# Condor2_80_Pin_REV_C.net
KiCad netlist of a schematic drawn in Altium Designer
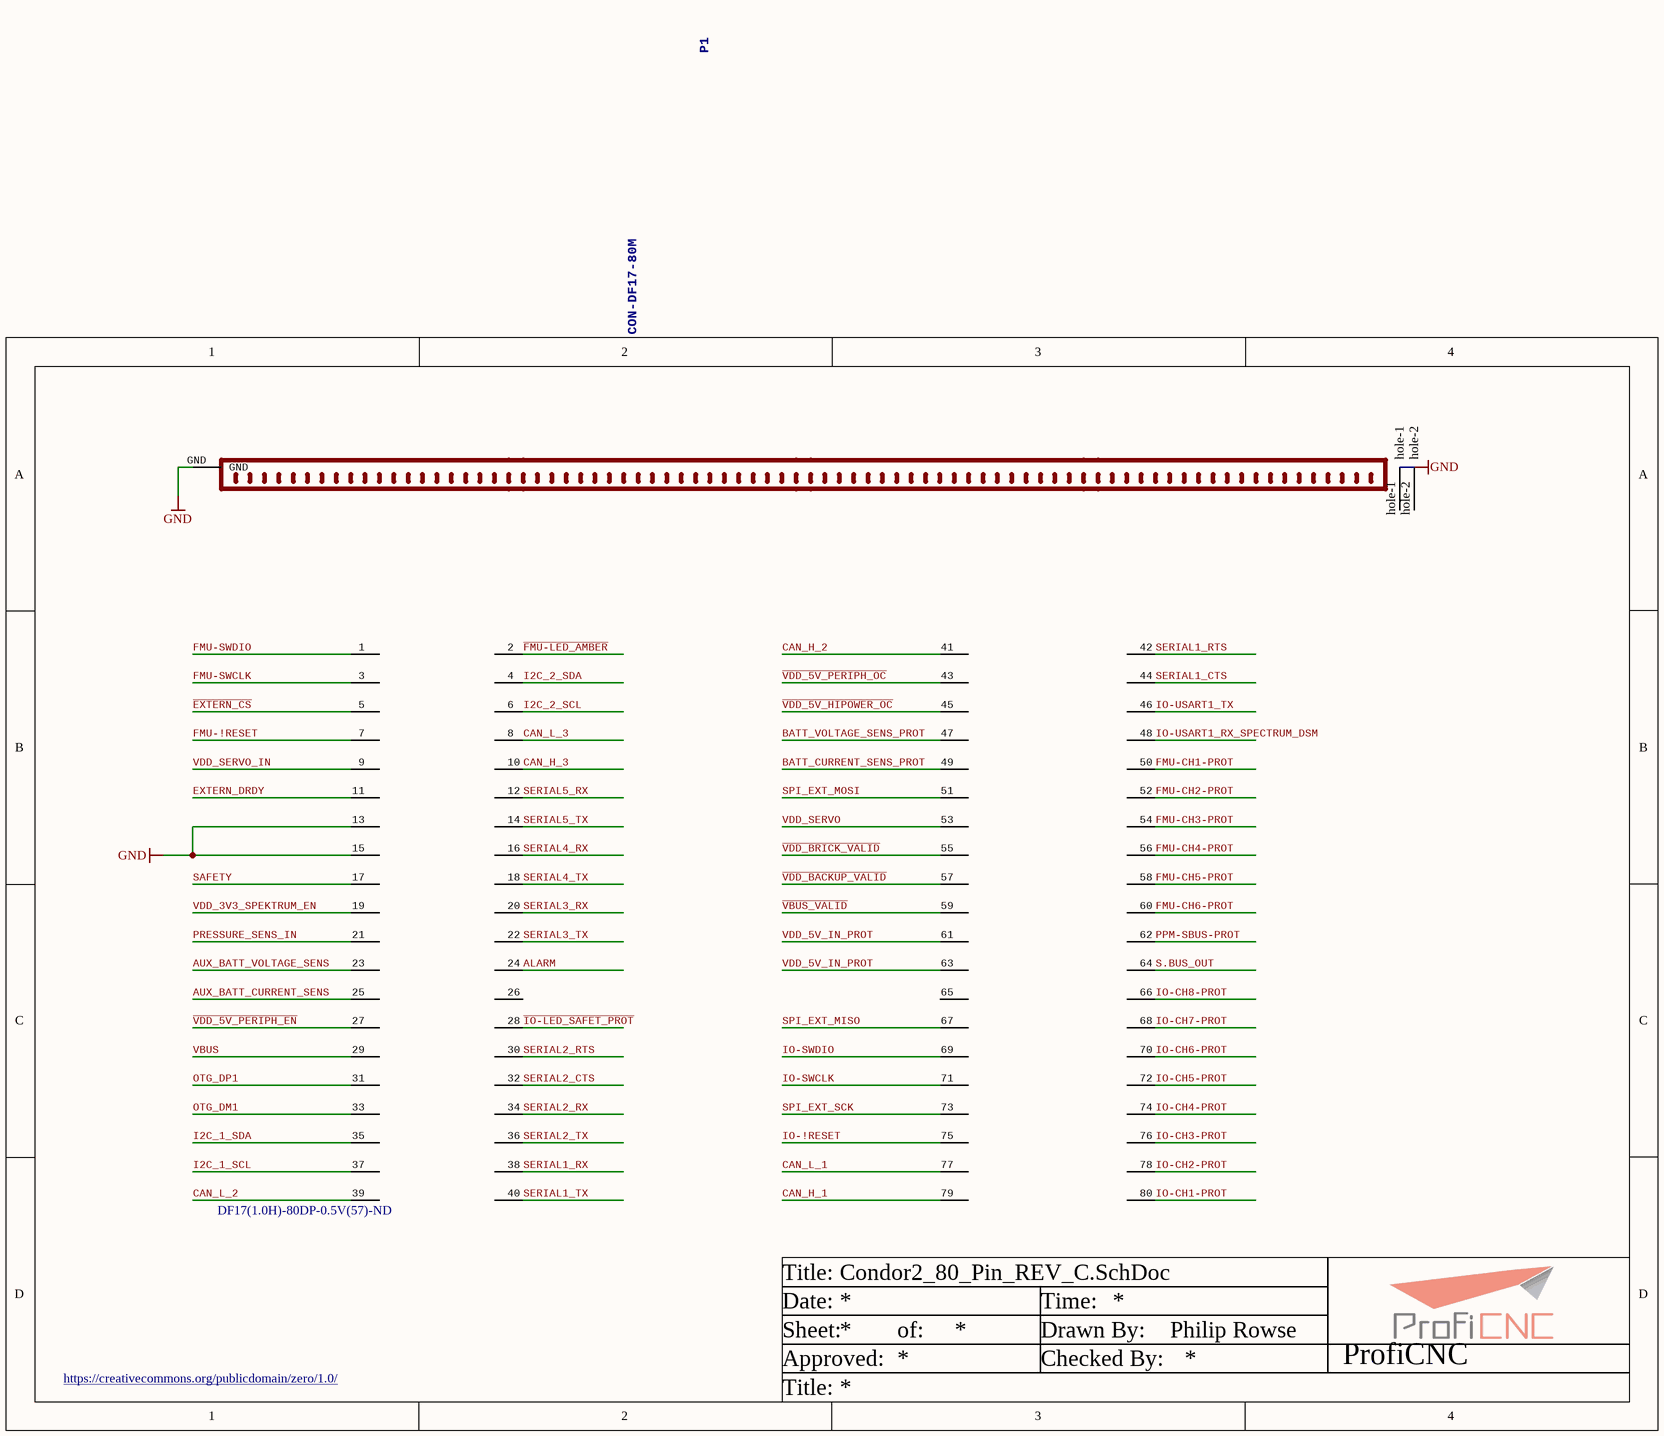
[diagram p0: Condor2_80_Pin_REV_C.SchDoc]

(export (version "E")
  (design (tool "Eeschema 10.0.6"))
  (components
    (comp (ref "P1")
      (value "CON-DF17-80M")
      (footprint "CON-DF17-80M")
      (description "Connector, Header, 80Pos, .5MM, DUAL, SMD, Au")
      (fields (field (name "SUPPLIER PART NUMBER 1") "DF17(1.0H)-80DP-0.5V(57)-ND"))
      (libsource (lib "CB_REV_C") (part "CON-DF17-80M"))
    )
  )
  (nets
    (net (code "1") (name "/ALARM") (class "Default")
      (node (ref "P1") (pin "24") (pinfunction "24_24") (pintype "passive"))
    )
    (net (code "2") (name "/AUX_BATT_CURRENT_SENS") (class "Default")
      (node (ref "P1") (pin "25") (pinfunction "25_25") (pintype "passive"))
    )
    (net (code "3") (name "/AUX_BATT_VOLTAGE_SENS") (class "Default")
      (node (ref "P1") (pin "23") (pinfunction "23_23") (pintype "passive"))
    )
    (net (code "4") (name "/BATT_CURRENT_SENS_PROT") (class "Default")
      (node (ref "P1") (pin "49") (pinfunction "49_49") (pintype "passive"))
    )
    (net (code "5") (name "/BATT_VOLTAGE_SENS_PROT") (class "Default")
      (node (ref "P1") (pin "47") (pinfunction "47_47") (pintype "passive"))
    )
    (net (code "6") (name "/CAN_H_1") (class "Default")
      (node (ref "P1") (pin "79") (pinfunction "79_79") (pintype "passive"))
    )
    (net (code "7") (name "/CAN_H_2") (class "Default")
      (node (ref "P1") (pin "41") (pinfunction "41_41") (pintype "passive"))
    )
    (net (code "8") (name "/CAN_H_3") (class "Default")
      (node (ref "P1") (pin "10") (pinfunction "10_10") (pintype "passive"))
    )
    (net (code "9") (name "/CAN_L_1") (class "Default")
      (node (ref "P1") (pin "77") (pinfunction "77_77") (pintype "passive"))
    )
    (net (code "10") (name "/CAN_L_2") (class "Default")
      (node (ref "P1") (pin "39") (pinfunction "39_39") (pintype "passive"))
    )
    (net (code "11") (name "/CAN_L_3") (class "Default")
      (node (ref "P1") (pin "8") (pinfunction "8_8") (pintype "passive"))
    )
    (net (code "12") (name "/EXTERN_DRDY") (class "Default")
      (node (ref "P1") (pin "11") (pinfunction "11_11") (pintype "passive"))
    )
    (net (code "13") (name "/FMU-!RESET") (class "Default")
      (node (ref "P1") (pin "7") (pinfunction "7_7") (pintype "passive"))
    )
    (net (code "14") (name "/FMU-CH1-PROT") (class "Default")
      (node (ref "P1") (pin "50") (pinfunction "50_50") (pintype "passive"))
    )
    (net (code "15") (name "/FMU-CH2-PROT") (class "Default")
      (node (ref "P1") (pin "52") (pinfunction "52_52") (pintype "passive"))
    )
    (net (code "16") (name "/FMU-CH3-PROT") (class "Default")
      (node (ref "P1") (pin "54") (pinfunction "54_54") (pintype "passive"))
    )
    (net (code "17") (name "/FMU-CH4-PROT") (class "Default")
      (node (ref "P1") (pin "56") (pinfunction "56_56") (pintype "passive"))
    )
    (net (code "18") (name "/FMU-CH5-PROT") (class "Default")
      (node (ref "P1") (pin "58") (pinfunction "58_58") (pintype "passive"))
    )
    (net (code "19") (name "/FMU-CH6-PROT") (class "Default")
      (node (ref "P1") (pin "60") (pinfunction "60_60") (pintype "passive"))
    )
    (net (code "20") (name "/FMU-SWCLK") (class "Default")
      (node (ref "P1") (pin "3") (pinfunction "3_3") (pintype "passive"))
    )
    (net (code "21") (name "/FMU-SWDIO") (class "Default")
      (node (ref "P1") (pin "1") (pinfunction "1_1") (pintype "passive"))
    )
    (net (code "22") (name "/I2C_1_SCL") (class "Default")
      (node (ref "P1") (pin "37") (pinfunction "37_37") (pintype "passive"))
    )
    (net (code "23") (name "/I2C_1_SDA") (class "Default")
      (node (ref "P1") (pin "35") (pinfunction "35_35") (pintype "passive"))
    )
    (net (code "24") (name "/I2C_2_SCL") (class "Default")
      (node (ref "P1") (pin "6") (pinfunction "6_6") (pintype "passive"))
    )
    (net (code "25") (name "/I2C_2_SDA") (class "Default")
      (node (ref "P1") (pin "4") (pinfunction "4_4") (pintype "passive"))
    )
    (net (code "26") (name "/IO-!RESET") (class "Default")
      (node (ref "P1") (pin "75") (pinfunction "75_75") (pintype "passive"))
    )
    (net (code "27") (name "/IO-CH1-PROT") (class "Default")
      (node (ref "P1") (pin "80") (pinfunction "80_80") (pintype "passive"))
    )
    (net (code "28") (name "/IO-CH2-PROT") (class "Default")
      (node (ref "P1") (pin "78") (pinfunction "78_78") (pintype "passive"))
    )
    (net (code "29") (name "/IO-CH3-PROT") (class "Default")
      (node (ref "P1") (pin "76") (pinfunction "76_76") (pintype "passive"))
    )
    (net (code "30") (name "/IO-CH4-PROT") (class "Default")
      (node (ref "P1") (pin "74") (pinfunction "74_74") (pintype "passive"))
    )
    (net (code "31") (name "/IO-CH5-PROT") (class "Default")
      (node (ref "P1") (pin "72") (pinfunction "72_72") (pintype "passive"))
    )
    (net (code "32") (name "/IO-CH6-PROT") (class "Default")
      (node (ref "P1") (pin "70") (pinfunction "70_70") (pintype "passive"))
    )
    (net (code "33") (name "/IO-CH7-PROT") (class "Default")
      (node (ref "P1") (pin "68") (pinfunction "68_68") (pintype "passive"))
    )
    (net (code "34") (name "/IO-CH8-PROT") (class "Default")
      (node (ref "P1") (pin "66") (pinfunction "66_66") (pintype "passive"))
    )
    (net (code "35") (name "/IO-SWCLK") (class "Default")
      (node (ref "P1") (pin "71") (pinfunction "71_71") (pintype "passive"))
    )
    (net (code "36") (name "/IO-SWDIO") (class "Default")
      (node (ref "P1") (pin "69") (pinfunction "69_69") (pintype "passive"))
    )
    (net (code "37") (name "/IO-USART1_RX_SPECTRUM_DSM") (class "Default")
      (node (ref "P1") (pin "48") (pinfunction "48_48") (pintype "passive"))
    )
    (net (code "38") (name "/IO-USART1_TX") (class "Default")
      (node (ref "P1") (pin "46") (pinfunction "46_46") (pintype "passive"))
    )
    (net (code "39") (name "/OTG_DM1") (class "Default")
      (node (ref "P1") (pin "33") (pinfunction "33_33") (pintype "passive"))
    )
    (net (code "40") (name "/OTG_DP1") (class "Default")
      (node (ref "P1") (pin "31") (pinfunction "31_31") (pintype "passive"))
    )
    (net (code "41") (name "/PPM-SBUS-PROT") (class "Default")
      (node (ref "P1") (pin "62") (pinfunction "62_62") (pintype "passive"))
    )
    (net (code "42") (name "/PRESSURE_SENS_IN") (class "Default")
      (node (ref "P1") (pin "21") (pinfunction "21_21") (pintype "passive"))
    )
    (net (code "43") (name "/S.BUS_OUT") (class "Default")
      (node (ref "P1") (pin "64") (pinfunction "64_64") (pintype "passive"))
    )
    (net (code "44") (name "/SAFETY") (class "Default")
      (node (ref "P1") (pin "17") (pinfunction "17_17") (pintype "passive"))
    )
    (net (code "45") (name "/SERIAL1_CTS") (class "Default")
      (node (ref "P1") (pin "44") (pinfunction "44_44") (pintype "passive"))
    )
    (net (code "46") (name "/SERIAL1_RTS") (class "Default")
      (node (ref "P1") (pin "42") (pinfunction "42_42") (pintype "passive"))
    )
    (net (code "47") (name "/SERIAL1_RX") (class "Default")
      (node (ref "P1") (pin "38") (pinfunction "38_38") (pintype "passive"))
    )
    (net (code "48") (name "/SERIAL1_TX") (class "Default")
      (node (ref "P1") (pin "40") (pinfunction "40_40") (pintype "passive"))
    )
    (net (code "49") (name "/SERIAL2_CTS") (class "Default")
      (node (ref "P1") (pin "32") (pinfunction "32_32") (pintype "passive"))
    )
    (net (code "50") (name "/SERIAL2_RTS") (class "Default")
      (node (ref "P1") (pin "30") (pinfunction "30_30") (pintype "passive"))
    )
    (net (code "51") (name "/SERIAL2_RX") (class "Default")
      (node (ref "P1") (pin "34") (pinfunction "34_34") (pintype "passive"))
    )
    (net (code "52") (name "/SERIAL2_TX") (class "Default")
      (node (ref "P1") (pin "36") (pinfunction "36_36") (pintype "passive"))
    )
    (net (code "53") (name "/SERIAL3_RX") (class "Default")
      (node (ref "P1") (pin "20") (pinfunction "20_20") (pintype "passive"))
    )
    (net (code "54") (name "/SERIAL3_TX") (class "Default")
      (node (ref "P1") (pin "22") (pinfunction "22_22") (pintype "passive"))
    )
    (net (code "55") (name "/SERIAL4_RX") (class "Default")
      (node (ref "P1") (pin "16") (pinfunction "16_16") (pintype "passive"))
    )
    (net (code "56") (name "/SERIAL4_TX") (class "Default")
      (node (ref "P1") (pin "18") (pinfunction "18_18") (pintype "passive"))
    )
    (net (code "57") (name "/SERIAL5_RX") (class "Default")
      (node (ref "P1") (pin "12") (pinfunction "12_12") (pintype "passive"))
    )
    (net (code "58") (name "/SERIAL5_TX") (class "Default")
      (node (ref "P1") (pin "14") (pinfunction "14_14") (pintype "passive"))
    )
    (net (code "59") (name "/SPI_EXT_MISO") (class "Default")
      (node (ref "P1") (pin "67") (pinfunction "67_67") (pintype "passive"))
    )
    (net (code "60") (name "/SPI_EXT_MOSI") (class "Default")
      (node (ref "P1") (pin "51") (pinfunction "51_51") (pintype "passive"))
    )
    (net (code "61") (name "/SPI_EXT_SCK") (class "Default")
      (node (ref "P1") (pin "73") (pinfunction "73_73") (pintype "passive"))
    )
    (net (code "62") (name "/VBUS") (class "Default")
      (node (ref "P1") (pin "29") (pinfunction "29_29") (pintype "passive"))
    )
    (net (code "63") (name "/VDD_3V3_SPEKTRUM_EN") (class "Default")
      (node (ref "P1") (pin "19") (pinfunction "19_19") (pintype "passive"))
    )
    (net (code "64") (name "/VDD_5V_IN_PROT") (class "Default")
      (node (ref "P1") (pin "61") (pinfunction "61_61") (pintype "passive"))
      (node (ref "P1") (pin "63") (pinfunction "63_63") (pintype "passive"))
    )
    (net (code "65") (name "/VDD_SERVO") (class "Default")
      (node (ref "P1") (pin "53") (pinfunction "53_53") (pintype "passive"))
    )
    (net (code "66") (name "/VDD_SERVO_IN") (class "Default")
      (node (ref "P1") (pin "9") (pinfunction "9_9") (pintype "passive"))
    )
    (net (code "67") (name "/~{EXTERN_CS}") (class "Default")
      (node (ref "P1") (pin "5") (pinfunction "5_5") (pintype "passive"))
    )
    (net (code "68") (name "/~{FMU-LED_AMBER}") (class "Default")
      (node (ref "P1") (pin "2") (pinfunction "2_2") (pintype "passive"))
    )
    (net (code "69") (name "/~{IO-LED_SAFET_PROT}") (class "Default")
      (node (ref "P1") (pin "28") (pinfunction "28_28") (pintype "passive"))
    )
    (net (code "70") (name "/~{VBUS_VALID}") (class "Default")
      (node (ref "P1") (pin "59") (pinfunction "59_59") (pintype "passive"))
    )
    (net (code "71") (name "/~{VDD_5V_HIPOWER_OC}") (class "Default")
      (node (ref "P1") (pin "45") (pinfunction "45_45") (pintype "passive"))
    )
    (net (code "72") (name "/~{VDD_5V_PERIPH_EN}") (class "Default")
      (node (ref "P1") (pin "27") (pinfunction "27_27") (pintype "passive"))
    )
    (net (code "73") (name "/~{VDD_5V_PERIPH_OC}") (class "Default")
      (node (ref "P1") (pin "43") (pinfunction "43_43") (pintype "passive"))
    )
    (net (code "74") (name "/~{VDD_BACKUP_VALID}") (class "Default")
      (node (ref "P1") (pin "57") (pinfunction "57_57") (pintype "passive"))
    )
    (net (code "75") (name "/~{VDD_BRICK_VALID}") (class "Default")
      (node (ref "P1") (pin "55") (pinfunction "55_55") (pintype "passive"))
    )
    (net (code "76") (name "GND") (class "Default")
      (node (ref "P1") (pin "13") (pinfunction "13_13") (pintype "passive"))
      (node (ref "P1") (pin "15") (pinfunction "15_15") (pintype "passive"))
      (node (ref "P1") (pin "GND") (pinfunction "GND_GND") (pintype "passive"))
    )
    (net (code "77") (name "unconnected-(P1-Pad26)") (class "Default")
      (node (ref "P1") (pin "26") (pinfunction "26_26") (pintype "passive"))
    )
    (net (code "78") (name "unconnected-(P1-Pad65)") (class "Default")
      (node (ref "P1") (pin "65") (pinfunction "65_65") (pintype "passive"))
    )
    (net (code "79") (name "unconnected-(P1-Padhole-1)") (class "Default")
      (node (ref "P1") (pin "hole-1") (pinfunction "hole-1_hole-1") (pintype "passive"))
    )
    (net (code "80") (name "unconnected-(P1-Padhole-2)") (class "Default")
      (node (ref "P1") (pin "hole-2") (pinfunction "hole-2_hole-2") (pintype "passive"))
    )
  )
)
